# LedPlaneControl.net
KiCad netlist of a schematic drawn in Altium Designer
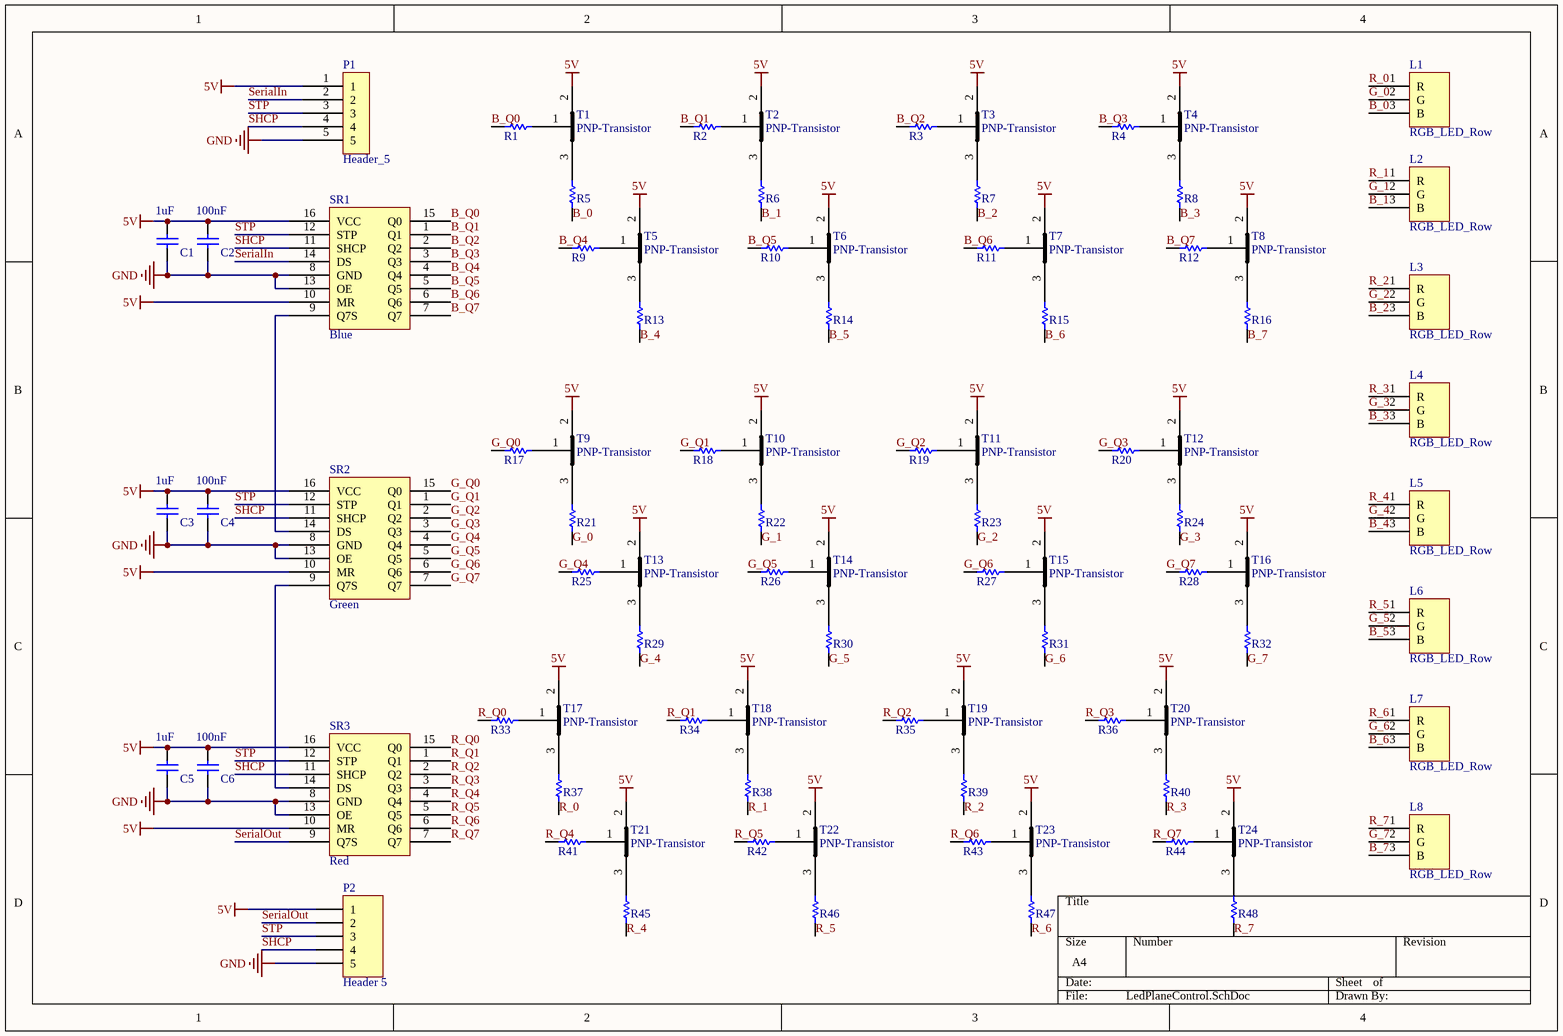
[diagram p0: LedPlaneControl.SchDoc]

(export (version "E")
  (design (tool "Eeschema 10.0.6"))
  (components
    (comp (ref "C1")
      (value "1uF")
      (footprint "CAPC1206(3216)190_L")
      (description "CAP 100nF 16V Â±1% 1206 (3216 Metric) Thickness 1.9mm SMD")
      (fields (field (name "TOLERANCE") "Â±1%") (field (name "Comment") "CAP 100nF 16V 1206(3216)"))
      (libsource (lib "Altium Content Vault") (part "CAP"))
    )
    (comp (ref "C2")
      (value "100nF")
      (footprint "CAPC1206(3216)190_L")
      (description "CAP 100nF 16V Â±1% 1206 (3216 Metric) Thickness 1.9mm SMD")
      (fields (field (name "TOLERANCE") "Â±1%") (field (name "Comment") "CAP 100nF 16V 1206(3216)"))
      (libsource (lib "Altium Content Vault") (part "CAP"))
    )
    (comp (ref "C3")
      (value "1uF")
      (footprint "CAPC1206(3216)190_L")
      (description "CAP 100nF 16V Â±1% 1206 (3216 Metric) Thickness 1.9mm SMD")
      (fields (field (name "TOLERANCE") "Â±1%") (field (name "Comment") "CAP 100nF 16V 1206(3216)"))
      (libsource (lib "Altium Content Vault") (part "CAP"))
    )
    (comp (ref "C4")
      (value "100nF")
      (footprint "CAPC1206(3216)190_L")
      (description "CAP 100nF 16V Â±1% 1206 (3216 Metric) Thickness 1.9mm SMD")
      (fields (field (name "TOLERANCE") "Â±1%") (field (name "Comment") "CAP 100nF 16V 1206(3216)"))
      (libsource (lib "Altium Content Vault") (part "CAP"))
    )
    (comp (ref "C5")
      (value "1uF")
      (footprint "CAPC1206(3216)190_L")
      (description "CAP 100nF 16V Â±1% 1206 (3216 Metric) Thickness 1.9mm SMD")
      (fields (field (name "TOLERANCE") "Â±1%") (field (name "Comment") "CAP 100nF 16V 1206(3216)"))
      (libsource (lib "Altium Content Vault") (part "CAP"))
    )
    (comp (ref "C6")
      (value "100nF")
      (footprint "CAPC1206(3216)190_L")
      (description "CAP 100nF 16V Â±1% 1206 (3216 Metric) Thickness 1.9mm SMD")
      (fields (field (name "TOLERANCE") "Â±1%") (field (name "Comment") "CAP 100nF 16V 1206(3216)"))
      (libsource (lib "Altium Content Vault") (part "CAP"))
    )
    (comp (ref "L1")
      (value "RGB_LED_Row")
      (footprint "LED_Row")
      (libsource (lib "RGB-Cube") (part "RGB_LED_Row"))
    )
    (comp (ref "L2")
      (value "RGB_LED_Row")
      (footprint "LED_Row")
      (libsource (lib "RGB-Cube") (part "RGB_LED_Row"))
    )
    (comp (ref "L3")
      (value "RGB_LED_Row")
      (footprint "LED_Row")
      (libsource (lib "RGB-Cube") (part "RGB_LED_Row"))
    )
    (comp (ref "L4")
      (value "RGB_LED_Row")
      (footprint "LED_Row")
      (libsource (lib "RGB-Cube") (part "RGB_LED_Row"))
    )
    (comp (ref "L5")
      (value "RGB_LED_Row")
      (footprint "LED_Row")
      (libsource (lib "RGB-Cube") (part "RGB_LED_Row"))
    )
    (comp (ref "L6")
      (value "RGB_LED_Row")
      (footprint "LED_Row")
      (libsource (lib "RGB-Cube") (part "RGB_LED_Row"))
    )
    (comp (ref "L7")
      (value "RGB_LED_Row")
      (footprint "LED_Row")
      (libsource (lib "RGB-Cube") (part "RGB_LED_Row"))
    )
    (comp (ref "L8")
      (value "RGB_LED_Row")
      (footprint "LED_Row")
      (libsource (lib "RGB-Cube") (part "RGB_LED_Row"))
    )
    (comp (ref "P1")
      (value "Header_5")
      (footprint "PinHeader")
      (libsource (lib "RGB-Cube") (part "Header_5"))
    )
    (comp (ref "P2")
      (value "Header 5")
      (footprint "HDR1X5")
      (description "Header, 5-Pin")
      (fields (field (name "PUBLISHER") "Altium Limited"))
      (libsource (lib "Miscellaneous Connectors") (part "Header 5"))
    )
    (comp (ref "R1")
      (value "43k 5% 1206(3216)")
      (footprint "RESC1206(3216)_M")
      (description "43k 0.25W 5% 1206 (3216 Metric)  SMD")
      (fields (field (name "TOLERANCE") "5 %") (field (name "POWER") "0.25 W"))
      (libsource (lib "Altium Content Vault") (part "CMP-1014-00009-1"))
    )
    (comp (ref "R2")
      (value "43k 5% 1206(3216)")
      (footprint "RESC1206(3216)_M")
      (description "43k 0.25W 5% 1206 (3216 Metric)  SMD")
      (fields (field (name "TOLERANCE") "5 %") (field (name "POWER") "0.25 W"))
      (libsource (lib "Altium Content Vault") (part "CMP-1014-00009-1"))
    )
    (comp (ref "R3")
      (value "43k 5% 1206(3216)")
      (footprint "RESC1206(3216)_M")
      (description "43k 0.25W 5% 1206 (3216 Metric)  SMD")
      (fields (field (name "TOLERANCE") "5 %") (field (name "POWER") "0.25 W"))
      (libsource (lib "Altium Content Vault") (part "CMP-1014-00009-1"))
    )
    (comp (ref "R4")
      (value "43k 5% 1206(3216)")
      (footprint "RESC1206(3216)_M")
      (description "43k 0.25W 5% 1206 (3216 Metric)  SMD")
      (fields (field (name "TOLERANCE") "5 %") (field (name "POWER") "0.25 W"))
      (libsource (lib "Altium Content Vault") (part "CMP-1014-00009-1"))
    )
    (comp (ref "R5")
      (value "2R 5% 1206(3216)")
      (footprint "RESC1206(3216)_M")
      (description "2R 0.25W 5% 1206 (3216 Metric)  SMD")
      (fields (field (name "TOLERANCE") "5 %") (field (name "POWER") "0.25 W"))
      (libsource (lib "Altium Content Vault") (part "CMP-1014-00009-1"))
    )
    (comp (ref "R6")
      (value "2R 5% 1206(3216)")
      (footprint "RESC1206(3216)_M")
      (description "2R 0.25W 5% 1206 (3216 Metric)  SMD")
      (fields (field (name "TOLERANCE") "5 %") (field (name "POWER") "0.25 W"))
      (libsource (lib "Altium Content Vault") (part "CMP-1014-00009-1"))
    )
    (comp (ref "R7")
      (value "2R 5% 1206(3216)")
      (footprint "RESC1206(3216)_M")
      (description "2R 0.25W 5% 1206 (3216 Metric)  SMD")
      (fields (field (name "TOLERANCE") "5 %") (field (name "POWER") "0.25 W"))
      (libsource (lib "Altium Content Vault") (part "CMP-1014-00009-1"))
    )
    (comp (ref "R8")
      (value "2R 5% 1206(3216)")
      (footprint "RESC1206(3216)_M")
      (description "2R 0.25W 5% 1206 (3216 Metric)  SMD")
      (fields (field (name "TOLERANCE") "5 %") (field (name "POWER") "0.25 W"))
      (libsource (lib "Altium Content Vault") (part "CMP-1014-00009-1"))
    )
    (comp (ref "R9")
      (value "43k 5% 1206(3216)")
      (footprint "RESC1206(3216)_M")
      (description "43k 0.25W 5% 1206 (3216 Metric)  SMD")
      (fields (field (name "TOLERANCE") "5 %") (field (name "POWER") "0.25 W"))
      (libsource (lib "Altium Content Vault") (part "CMP-1014-00009-1"))
    )
    (comp (ref "R10")
      (value "43k 5% 1206(3216)")
      (footprint "RESC1206(3216)_M")
      (description "43k 0.25W 5% 1206 (3216 Metric)  SMD")
      (fields (field (name "TOLERANCE") "5 %") (field (name "POWER") "0.25 W"))
      (libsource (lib "Altium Content Vault") (part "CMP-1014-00009-1"))
    )
    (comp (ref "R11")
      (value "43k 5% 1206(3216)")
      (footprint "RESC1206(3216)_M")
      (description "43k 0.25W 5% 1206 (3216 Metric)  SMD")
      (fields (field (name "TOLERANCE") "5 %") (field (name "POWER") "0.25 W"))
      (libsource (lib "Altium Content Vault") (part "CMP-1014-00009-1"))
    )
    (comp (ref "R12")
      (value "43k 5% 1206(3216)")
      (footprint "RESC1206(3216)_M")
      (description "43k 0.25W 5% 1206 (3216 Metric)  SMD")
      (fields (field (name "TOLERANCE") "5 %") (field (name "POWER") "0.25 W"))
      (libsource (lib "Altium Content Vault") (part "CMP-1014-00009-1"))
    )
    (comp (ref "R13")
      (value "2R 5% 1206(3216)")
      (footprint "RESC1206(3216)_M")
      (description "2R 0.25W 5% 1206 (3216 Metric)  SMD")
      (fields (field (name "TOLERANCE") "5 %") (field (name "POWER") "0.25 W"))
      (libsource (lib "Altium Content Vault") (part "CMP-1014-00009-1"))
    )
    (comp (ref "R14")
      (value "2R 5% 1206(3216)")
      (footprint "RESC1206(3216)_M")
      (description "2R 0.25W 5% 1206 (3216 Metric)  SMD")
      (fields (field (name "TOLERANCE") "5 %") (field (name "POWER") "0.25 W"))
      (libsource (lib "Altium Content Vault") (part "CMP-1014-00009-1"))
    )
    (comp (ref "R15")
      (value "2R 5% 1206(3216)")
      (footprint "RESC1206(3216)_M")
      (description "2R 0.25W 5% 1206 (3216 Metric)  SMD")
      (fields (field (name "TOLERANCE") "5 %") (field (name "POWER") "0.25 W"))
      (libsource (lib "Altium Content Vault") (part "CMP-1014-00009-1"))
    )
    (comp (ref "R16")
      (value "2R 5% 1206(3216)")
      (footprint "RESC1206(3216)_M")
      (description "2R 0.25W 5% 1206 (3216 Metric)  SMD")
      (fields (field (name "TOLERANCE") "5 %") (field (name "POWER") "0.25 W"))
      (libsource (lib "Altium Content Vault") (part "CMP-1014-00009-1"))
    )
    (comp (ref "R17")
      (value "43k 5% 1206(3216)")
      (footprint "RESC1206(3216)_M")
      (description "43k 0.25W 5% 1206 (3216 Metric)  SMD")
      (fields (field (name "TOLERANCE") "5 %") (field (name "POWER") "0.25 W"))
      (libsource (lib "Altium Content Vault") (part "CMP-1014-00009-1"))
    )
    (comp (ref "R18")
      (value "43k 5% 1206(3216)")
      (footprint "RESC1206(3216)_M")
      (description "43k 0.25W 5% 1206 (3216 Metric)  SMD")
      (fields (field (name "TOLERANCE") "5 %") (field (name "POWER") "0.25 W"))
      (libsource (lib "Altium Content Vault") (part "CMP-1014-00009-1"))
    )
    (comp (ref "R19")
      (value "43k 5% 1206(3216)")
      (footprint "RESC1206(3216)_M")
      (description "43k 0.25W 5% 1206 (3216 Metric)  SMD")
      (fields (field (name "TOLERANCE") "5 %") (field (name "POWER") "0.25 W"))
      (libsource (lib "Altium Content Vault") (part "CMP-1014-00009-1"))
    )
    (comp (ref "R20")
      (value "43k 5% 1206(3216)")
      (footprint "RESC1206(3216)_M")
      (description "43k 0.25W 5% 1206 (3216 Metric)  SMD")
      (fields (field (name "TOLERANCE") "5 %") (field (name "POWER") "0.25 W"))
      (libsource (lib "Altium Content Vault") (part "CMP-1014-00009-1"))
    )
    (comp (ref "R21")
      (value "2R 5% 1206(3216)")
      (footprint "RESC1206(3216)_M")
      (description "2R 0.25W 5% 1206 (3216 Metric)  SMD")
      (fields (field (name "TOLERANCE") "5 %") (field (name "POWER") "0.25 W"))
      (libsource (lib "Altium Content Vault") (part "CMP-1014-00009-1"))
    )
    (comp (ref "R22")
      (value "2R 5% 1206(3216)")
      (footprint "RESC1206(3216)_M")
      (description "2R 0.25W 5% 1206 (3216 Metric)  SMD")
      (fields (field (name "TOLERANCE") "5 %") (field (name "POWER") "0.25 W"))
      (libsource (lib "Altium Content Vault") (part "CMP-1014-00009-1"))
    )
    (comp (ref "R23")
      (value "2R 5% 1206(3216)")
      (footprint "RESC1206(3216)_M")
      (description "2R 0.25W 5% 1206 (3216 Metric)  SMD")
      (fields (field (name "TOLERANCE") "5 %") (field (name "POWER") "0.25 W"))
      (libsource (lib "Altium Content Vault") (part "CMP-1014-00009-1"))
    )
    (comp (ref "R24")
      (value "2R 5% 1206(3216)")
      (footprint "RESC1206(3216)_M")
      (description "2R 0.25W 5% 1206 (3216 Metric)  SMD")
      (fields (field (name "TOLERANCE") "5 %") (field (name "POWER") "0.25 W"))
      (libsource (lib "Altium Content Vault") (part "CMP-1014-00009-1"))
    )
    (comp (ref "R25")
      (value "43k 5% 1206(3216)")
      (footprint "RESC1206(3216)_M")
      (description "43k 0.25W 5% 1206 (3216 Metric)  SMD")
      (fields (field (name "TOLERANCE") "5 %") (field (name "POWER") "0.25 W"))
      (libsource (lib "Altium Content Vault") (part "CMP-1014-00009-1"))
    )
    (comp (ref "R26")
      (value "43k 5% 1206(3216)")
      (footprint "RESC1206(3216)_M")
      (description "43k 0.25W 5% 1206 (3216 Metric)  SMD")
      (fields (field (name "TOLERANCE") "5 %") (field (name "POWER") "0.25 W"))
      (libsource (lib "Altium Content Vault") (part "CMP-1014-00009-1"))
    )
    (comp (ref "R27")
      (value "43k 5% 1206(3216)")
      (footprint "RESC1206(3216)_M")
      (description "43k 0.25W 5% 1206 (3216 Metric)  SMD")
      (fields (field (name "TOLERANCE") "5 %") (field (name "POWER") "0.25 W"))
      (libsource (lib "Altium Content Vault") (part "CMP-1014-00009-1"))
    )
    (comp (ref "R28")
      (value "43k 5% 1206(3216)")
      (footprint "RESC1206(3216)_M")
      (description "43k 0.25W 5% 1206 (3216 Metric)  SMD")
      (fields (field (name "TOLERANCE") "5 %") (field (name "POWER") "0.25 W"))
      (libsource (lib "Altium Content Vault") (part "CMP-1014-00009-1"))
    )
    (comp (ref "R29")
      (value "2R 5% 1206(3216)")
      (footprint "RESC1206(3216)_M")
      (description "2R 0.25W 5% 1206 (3216 Metric)  SMD")
      (fields (field (name "TOLERANCE") "5 %") (field (name "POWER") "0.25 W"))
      (libsource (lib "Altium Content Vault") (part "CMP-1014-00009-1"))
    )
    (comp (ref "R30")
      (value "2R 5% 1206(3216)")
      (footprint "RESC1206(3216)_M")
      (description "2R 0.25W 5% 1206 (3216 Metric)  SMD")
      (fields (field (name "TOLERANCE") "5 %") (field (name "POWER") "0.25 W"))
      (libsource (lib "Altium Content Vault") (part "CMP-1014-00009-1"))
    )
    (comp (ref "R31")
      (value "2R 5% 1206(3216)")
      (footprint "RESC1206(3216)_M")
      (description "2R 0.25W 5% 1206 (3216 Metric)  SMD")
      (fields (field (name "TOLERANCE") "5 %") (field (name "POWER") "0.25 W"))
      (libsource (lib "Altium Content Vault") (part "CMP-1014-00009-1"))
    )
    (comp (ref "R32")
      (value "2R 5% 1206(3216)")
      (footprint "RESC1206(3216)_M")
      (description "2R 0.25W 5% 1206 (3216 Metric)  SMD")
      (fields (field (name "TOLERANCE") "5 %") (field (name "POWER") "0.25 W"))
      (libsource (lib "Altium Content Vault") (part "CMP-1014-00009-1"))
    )
    (comp (ref "R33")
      (value "43k 5% 1206(3216)")
      (footprint "RESC1206(3216)_M")
      (description "43k 0.25W 5% 1206 (3216 Metric)  SMD")
      (fields (field (name "TOLERANCE") "5 %") (field (name "POWER") "0.25 W"))
      (libsource (lib "Altium Content Vault") (part "CMP-1014-00009-1"))
    )
    (comp (ref "R34")
      (value "43k 5% 1206(3216)")
      (footprint "RESC1206(3216)_M")
      (description "43k 0.25W 5% 1206 (3216 Metric)  SMD")
      (fields (field (name "TOLERANCE") "5 %") (field (name "POWER") "0.25 W"))
      (libsource (lib "Altium Content Vault") (part "CMP-1014-00009-1"))
    )
    (comp (ref "R35")
      (value "43k 5% 1206(3216)")
      (footprint "RESC1206(3216)_M")
      (description "43k 0.25W 5% 1206 (3216 Metric)  SMD")
      (fields (field (name "TOLERANCE") "5 %") (field (name "POWER") "0.25 W"))
      (libsource (lib "Altium Content Vault") (part "CMP-1014-00009-1"))
    )
    (comp (ref "R36")
      (value "43k 5% 1206(3216)")
      (footprint "RESC1206(3216)_M")
      (description "43k 0.25W 5% 1206 (3216 Metric)  SMD")
      (fields (field (name "TOLERANCE") "5 %") (field (name "POWER") "0.25 W"))
      (libsource (lib "Altium Content Vault") (part "CMP-1014-00009-1"))
    )
    (comp (ref "R37")
      (value "2R 5% 1206(3216)")
      (footprint "RESC1206(3216)_M")
      (description "2R 0.25W 5% 1206 (3216 Metric)  SMD")
      (fields (field (name "TOLERANCE") "5 %") (field (name "POWER") "0.25 W"))
      (libsource (lib "Altium Content Vault") (part "CMP-1014-00009-1"))
    )
    (comp (ref "R38")
      (value "2R 5% 1206(3216)")
      (footprint "RESC1206(3216)_M")
      (description "2R 0.25W 5% 1206 (3216 Metric)  SMD")
      (fields (field (name "TOLERANCE") "5 %") (field (name "POWER") "0.25 W"))
      (libsource (lib "Altium Content Vault") (part "CMP-1014-00009-1"))
    )
    (comp (ref "R39")
      (value "2R 5% 1206(3216)")
      (footprint "RESC1206(3216)_M")
      (description "2R 0.25W 5% 1206 (3216 Metric)  SMD")
      (fields (field (name "TOLERANCE") "5 %") (field (name "POWER") "0.25 W"))
      (libsource (lib "Altium Content Vault") (part "CMP-1014-00009-1"))
    )
    (comp (ref "R40")
      (value "2R 5% 1206(3216)")
      (footprint "RESC1206(3216)_M")
      (description "2R 0.25W 5% 1206 (3216 Metric)  SMD")
      (fields (field (name "TOLERANCE") "5 %") (field (name "POWER") "0.25 W"))
      (libsource (lib "Altium Content Vault") (part "CMP-1014-00009-1"))
    )
    (comp (ref "R41")
      (value "43k 5% 1206(3216)")
      (footprint "RESC1206(3216)_M")
      (description "43k 0.25W 5% 1206 (3216 Metric)  SMD")
      (fields (field (name "TOLERANCE") "5 %") (field (name "POWER") "0.25 W"))
      (libsource (lib "Altium Content Vault") (part "CMP-1014-00009-1"))
    )
    (comp (ref "R42")
      (value "43k 5% 1206(3216)")
      (footprint "RESC1206(3216)_M")
      (description "43k 0.25W 5% 1206 (3216 Metric)  SMD")
      (fields (field (name "TOLERANCE") "5 %") (field (name "POWER") "0.25 W"))
      (libsource (lib "Altium Content Vault") (part "CMP-1014-00009-1"))
    )
    (comp (ref "R43")
      (value "43k 5% 1206(3216)")
      (footprint "RESC1206(3216)_M")
      (description "43k 0.25W 5% 1206 (3216 Metric)  SMD")
      (fields (field (name "TOLERANCE") "5 %") (field (name "POWER") "0.25 W"))
      (libsource (lib "Altium Content Vault") (part "CMP-1014-00009-1"))
    )
    (comp (ref "R44")
      (value "43k 5% 1206(3216)")
      (footprint "RESC1206(3216)_M")
      (description "43k 0.25W 5% 1206 (3216 Metric)  SMD")
      (fields (field (name "TOLERANCE") "5 %") (field (name "POWER") "0.25 W"))
      (libsource (lib "Altium Content Vault") (part "CMP-1014-00009-1"))
    )
    (comp (ref "R45")
      (value "2R 5% 1206(3216)")
      (footprint "RESC1206(3216)_M")
      (description "2R 0.25W 5% 1206 (3216 Metric)  SMD")
      (fields (field (name "TOLERANCE") "5 %") (field (name "POWER") "0.25 W"))
      (libsource (lib "Altium Content Vault") (part "CMP-1014-00009-1"))
    )
    (comp (ref "R46")
      (value "2R 5% 1206(3216)")
      (footprint "RESC1206(3216)_M")
      (description "2R 0.25W 5% 1206 (3216 Metric)  SMD")
      (fields (field (name "TOLERANCE") "5 %") (field (name "POWER") "0.25 W"))
      (libsource (lib "Altium Content Vault") (part "CMP-1014-00009-1"))
    )
    (comp (ref "R47")
      (value "2R 5% 1206(3216)")
      (footprint "RESC1206(3216)_M")
      (description "2R 0.25W 5% 1206 (3216 Metric)  SMD")
      (fields (field (name "TOLERANCE") "5 %") (field (name "POWER") "0.25 W"))
      (libsource (lib "Altium Content Vault") (part "CMP-1014-00009-1"))
    )
    (comp (ref "R48")
      (value "2R 5% 1206(3216)")
      (footprint "RESC1206(3216)_M")
      (description "2R 0.25W 5% 1206 (3216 Metric)  SMD")
      (fields (field (name "TOLERANCE") "5 %") (field (name "POWER") "0.25 W"))
      (libsource (lib "Altium Content Vault") (part "CMP-1014-00009-1"))
    )
    (comp (ref "SR1")
      (value "Blue")
      (footprint "SOP16")
      (description "74HC595 Farnell:  2098004")
      (libsource (lib "RGB-Cube") (part "74HC595"))
    )
    (comp (ref "SR2")
      (value "Green")
      (footprint "SOP16")
      (description "74HC595 Farnell:  2098004")
      (libsource (lib "RGB-Cube") (part "74HC595"))
    )
    (comp (ref "SR3")
      (value "Red")
      (footprint "SOP16")
      (description "74HC595 Farnell:  2098004")
      (libsource (lib "RGB-Cube") (part "74HC595"))
    )
    (comp (ref "T1")
      (value "PNP-Transistor")
      (footprint "SOT-223")
      (description "Reichelt: BCP 51-16 NXP")
      (libsource (lib "RGB-Cube") (part "PNP-Transistor"))
    )
    (comp (ref "T2")
      (value "PNP-Transistor")
      (footprint "SOT-223")
      (description "Reichelt: BCP 51-16 NXP")
      (libsource (lib "RGB-Cube") (part "PNP-Transistor"))
    )
    (comp (ref "T3")
      (value "PNP-Transistor")
      (footprint "SOT-223")
      (description "Reichelt: BCP 51-16 NXP")
      (libsource (lib "RGB-Cube") (part "PNP-Transistor"))
    )
    (comp (ref "T4")
      (value "PNP-Transistor")
      (footprint "SOT-223")
      (description "Reichelt: BCP 51-16 NXP")
      (libsource (lib "RGB-Cube") (part "PNP-Transistor"))
    )
    (comp (ref "T5")
      (value "PNP-Transistor")
      (footprint "SOT-223")
      (description "Reichelt: BCP 51-16 NXP")
      (libsource (lib "RGB-Cube") (part "PNP-Transistor"))
    )
    (comp (ref "T6")
      (value "PNP-Transistor")
      (footprint "SOT-223")
      (description "Reichelt: BCP 51-16 NXP")
      (libsource (lib "RGB-Cube") (part "PNP-Transistor"))
    )
    (comp (ref "T7")
      (value "PNP-Transistor")
      (footprint "SOT-223")
      (description "Reichelt: BCP 51-16 NXP")
      (libsource (lib "RGB-Cube") (part "PNP-Transistor"))
    )
    (comp (ref "T8")
      (value "PNP-Transistor")
      (footprint "SOT-223")
      (description "Reichelt: BCP 51-16 NXP")
      (libsource (lib "RGB-Cube") (part "PNP-Transistor"))
    )
    (comp (ref "T9")
      (value "PNP-Transistor")
      (footprint "SOT-223")
      (description "Reichelt: BCP 51-16 NXP")
      (libsource (lib "RGB-Cube") (part "PNP-Transistor"))
    )
    (comp (ref "T10")
      (value "PNP-Transistor")
      (footprint "SOT-223")
      (description "Reichelt: BCP 51-16 NXP")
      (libsource (lib "RGB-Cube") (part "PNP-Transistor"))
    )
    (comp (ref "T11")
      (value "PNP-Transistor")
      (footprint "SOT-223")
      (description "Reichelt: BCP 51-16 NXP")
      (libsource (lib "RGB-Cube") (part "PNP-Transistor"))
    )
    (comp (ref "T12")
      (value "PNP-Transistor")
      (footprint "SOT-223")
      (description "Reichelt: BCP 51-16 NXP")
      (libsource (lib "RGB-Cube") (part "PNP-Transistor"))
    )
    (comp (ref "T13")
      (value "PNP-Transistor")
      (footprint "SOT-223")
      (description "Reichelt: BCP 51-16 NXP")
      (libsource (lib "RGB-Cube") (part "PNP-Transistor"))
    )
    (comp (ref "T14")
      (value "PNP-Transistor")
      (footprint "SOT-223")
      (description "Reichelt: BCP 51-16 NXP")
      (libsource (lib "RGB-Cube") (part "PNP-Transistor"))
    )
    (comp (ref "T15")
      (value "PNP-Transistor")
      (footprint "SOT-223")
      (description "Reichelt: BCP 51-16 NXP")
      (libsource (lib "RGB-Cube") (part "PNP-Transistor"))
    )
    (comp (ref "T16")
      (value "PNP-Transistor")
      (footprint "SOT-223")
      (description "Reichelt: BCP 51-16 NXP")
      (libsource (lib "RGB-Cube") (part "PNP-Transistor"))
    )
    (comp (ref "T17")
      (value "PNP-Transistor")
      (footprint "SOT-223")
      (description "Reichelt: BCP 51-16 NXP")
      (libsource (lib "RGB-Cube") (part "PNP-Transistor"))
    )
    (comp (ref "T18")
      (value "PNP-Transistor")
      (footprint "SOT-223")
      (description "Reichelt: BCP 51-16 NXP")
      (libsource (lib "RGB-Cube") (part "PNP-Transistor"))
    )
    (comp (ref "T19")
      (value "PNP-Transistor")
      (footprint "SOT-223")
      (description "Reichelt: BCP 51-16 NXP")
      (libsource (lib "RGB-Cube") (part "PNP-Transistor"))
    )
    (comp (ref "T20")
      (value "PNP-Transistor")
      (footprint "SOT-223")
      (description "Reichelt: BCP 51-16 NXP")
      (libsource (lib "RGB-Cube") (part "PNP-Transistor"))
    )
    (comp (ref "T21")
      (value "PNP-Transistor")
      (footprint "SOT-223")
      (description "Reichelt: BCP 51-16 NXP")
      (libsource (lib "RGB-Cube") (part "PNP-Transistor"))
    )
    (comp (ref "T22")
      (value "PNP-Transistor")
      (footprint "SOT-223")
      (description "Reichelt: BCP 51-16 NXP")
      (libsource (lib "RGB-Cube") (part "PNP-Transistor"))
    )
    (comp (ref "T23")
      (value "PNP-Transistor")
      (footprint "SOT-223")
      (description "Reichelt: BCP 51-16 NXP")
      (libsource (lib "RGB-Cube") (part "PNP-Transistor"))
    )
    (comp (ref "T24")
      (value "PNP-Transistor")
      (footprint "SOT-223")
      (description "Reichelt: BCP 51-16 NXP")
      (libsource (lib "RGB-Cube") (part "PNP-Transistor"))
    )
  )
  (nets
    (net (code "2") (name "/B_0") (class "Default")
      (node (ref "L1") (pin "3") (pinfunction "B_3") (pintype "passive"))
      (node (ref "R5") (pin "1") (pinfunction "1_1") (pintype "passive"))
    )
    (net (code "3") (name "/B_1") (class "Default")
      (node (ref "L2") (pin "3") (pinfunction "B_3") (pintype "passive"))
      (node (ref "R6") (pin "1") (pinfunction "1_1") (pintype "passive"))
    )
    (net (code "4") (name "/B_2") (class "Default")
      (node (ref "L3") (pin "3") (pinfunction "B_3") (pintype "passive"))
      (node (ref "R7") (pin "1") (pinfunction "1_1") (pintype "passive"))
    )
    (net (code "5") (name "/B_3") (class "Default")
      (node (ref "L4") (pin "3") (pinfunction "B_3") (pintype "passive"))
      (node (ref "R8") (pin "1") (pinfunction "1_1") (pintype "passive"))
    )
    (net (code "6") (name "/B_4") (class "Default")
      (node (ref "L5") (pin "3") (pinfunction "B_3") (pintype "passive"))
      (node (ref "R13") (pin "1") (pinfunction "1_1") (pintype "passive"))
    )
    (net (code "7") (name "/B_5") (class "Default")
      (node (ref "L6") (pin "3") (pinfunction "B_3") (pintype "passive"))
      (node (ref "R14") (pin "1") (pinfunction "1_1") (pintype "passive"))
    )
    (net (code "8") (name "/B_6") (class "Default")
      (node (ref "L7") (pin "3") (pinfunction "B_3") (pintype "passive"))
      (node (ref "R15") (pin "1") (pinfunction "1_1") (pintype "passive"))
    )
    (net (code "9") (name "/B_7") (class "Default")
      (node (ref "L8") (pin "3") (pinfunction "B_3") (pintype "passive"))
      (node (ref "R16") (pin "1") (pinfunction "1_1") (pintype "passive"))
    )
    (net (code "10") (name "/B_Q0") (class "Default")
      (node (ref "R1") (pin "1") (pinfunction "1_1") (pintype "passive"))
      (node (ref "SR1") (pin "15") (pinfunction "Q0_15") (pintype "passive"))
    )
    (net (code "11") (name "/B_Q1") (class "Default")
      (node (ref "R2") (pin "1") (pinfunction "1_1") (pintype "passive"))
      (node (ref "SR1") (pin "1") (pinfunction "Q1_1") (pintype "passive"))
    )
    (net (code "12") (name "/B_Q2") (class "Default")
      (node (ref "R3") (pin "1") (pinfunction "1_1") (pintype "passive"))
      (node (ref "SR1") (pin "2") (pinfunction "Q2_2") (pintype "passive"))
    )
    (net (code "13") (name "/B_Q3") (class "Default")
      (node (ref "R4") (pin "1") (pinfunction "1_1") (pintype "passive"))
      (node (ref "SR1") (pin "3") (pinfunction "Q3_3") (pintype "passive"))
    )
    (net (code "14") (name "/B_Q4") (class "Default")
      (node (ref "R9") (pin "1") (pinfunction "1_1") (pintype "passive"))
      (node (ref "SR1") (pin "4") (pinfunction "Q4_4") (pintype "passive"))
    )
    (net (code "15") (name "/B_Q5") (class "Default")
      (node (ref "R10") (pin "1") (pinfunction "1_1") (pintype "passive"))
      (node (ref "SR1") (pin "5") (pinfunction "Q5_5") (pintype "passive"))
    )
    (net (code "16") (name "/B_Q6") (class "Default")
      (node (ref "R11") (pin "1") (pinfunction "1_1") (pintype "passive"))
      (node (ref "SR1") (pin "6") (pinfunction "Q6_6") (pintype "passive"))
    )
    (net (code "17") (name "/B_Q7") (class "Default")
      (node (ref "R12") (pin "1") (pinfunction "1_1") (pintype "passive"))
      (node (ref "SR1") (pin "7") (pinfunction "Q7_7") (pintype "passive"))
    )
    (net (code "18") (name "/G_0") (class "Default")
      (node (ref "L1") (pin "2") (pinfunction "G_2") (pintype "passive"))
      (node (ref "R21") (pin "1") (pinfunction "1_1") (pintype "passive"))
    )
    (net (code "19") (name "/G_1") (class "Default")
      (node (ref "L2") (pin "2") (pinfunction "G_2") (pintype "passive"))
      (node (ref "R22") (pin "1") (pinfunction "1_1") (pintype "passive"))
    )
    (net (code "20") (name "/G_2") (class "Default")
      (node (ref "L3") (pin "2") (pinfunction "G_2") (pintype "passive"))
      (node (ref "R23") (pin "1") (pinfunction "1_1") (pintype "passive"))
    )
    (net (code "21") (name "/G_3") (class "Default")
      (node (ref "L4") (pin "2") (pinfunction "G_2") (pintype "passive"))
      (node (ref "R24") (pin "1") (pinfunction "1_1") (pintype "passive"))
    )
    (net (code "22") (name "/G_4") (class "Default")
      (node (ref "L5") (pin "2") (pinfunction "G_2") (pintype "passive"))
      (node (ref "R29") (pin "1") (pinfunction "1_1") (pintype "passive"))
    )
    (net (code "23") (name "/G_5") (class "Default")
      (node (ref "L6") (pin "2") (pinfunction "G_2") (pintype "passive"))
      (node (ref "R30") (pin "1") (pinfunction "1_1") (pintype "passive"))
    )
    (net (code "24") (name "/G_6") (class "Default")
      (node (ref "L7") (pin "2") (pinfunction "G_2") (pintype "passive"))
      (node (ref "R31") (pin "1") (pinfunction "1_1") (pintype "passive"))
    )
    (net (code "25") (name "/G_7") (class "Default")
      (node (ref "L8") (pin "2") (pinfunction "G_2") (pintype "passive"))
      (node (ref "R32") (pin "1") (pinfunction "1_1") (pintype "passive"))
    )
    (net (code "26") (name "/G_Q0") (class "Default")
      (node (ref "R17") (pin "1") (pinfunction "1_1") (pintype "passive"))
      (node (ref "SR2") (pin "15") (pinfunction "Q0_15") (pintype "passive"))
    )
    (net (code "27") (name "/G_Q1") (class "Default")
      (node (ref "R18") (pin "1") (pinfunction "1_1") (pintype "passive"))
      (node (ref "SR2") (pin "1") (pinfunction "Q1_1") (pintype "passive"))
    )
    (net (code "28") (name "/G_Q2") (class "Default")
      (node (ref "R19") (pin "1") (pinfunction "1_1") (pintype "passive"))
      (node (ref "SR2") (pin "2") (pinfunction "Q2_2") (pintype "passive"))
    )
    (net (code "29") (name "/G_Q3") (class "Default")
      (node (ref "R20") (pin "1") (pinfunction "1_1") (pintype "passive"))
      (node (ref "SR2") (pin "3") (pinfunction "Q3_3") (pintype "passive"))
    )
    (net (code "30") (name "/G_Q4") (class "Default")
      (node (ref "R25") (pin "1") (pinfunction "1_1") (pintype "passive"))
      (node (ref "SR2") (pin "4") (pinfunction "Q4_4") (pintype "passive"))
    )
    (net (code "31") (name "/G_Q5") (class "Default")
      (node (ref "R26") (pin "1") (pinfunction "1_1") (pintype "passive"))
      (node (ref "SR2") (pin "5") (pinfunction "Q5_5") (pintype "passive"))
    )
    (net (code "32") (name "/G_Q6") (class "Default")
      (node (ref "R27") (pin "1") (pinfunction "1_1") (pintype "passive"))
      (node (ref "SR2") (pin "6") (pinfunction "Q6_6") (pintype "passive"))
    )
    (net (code "33") (name "/G_Q7") (class "Default")
      (node (ref "R28") (pin "1") (pinfunction "1_1") (pintype "passive"))
      (node (ref "SR2") (pin "7") (pinfunction "Q7_7") (pintype "passive"))
    )
    (net (code "34") (name "/R_0") (class "Default")
      (node (ref "L1") (pin "1") (pinfunction "R_1") (pintype "passive"))
      (node (ref "R37") (pin "1") (pinfunction "1_1") (pintype "passive"))
    )
    (net (code "35") (name "/R_1") (class "Default")
      (node (ref "L2") (pin "1") (pinfunction "R_1") (pintype "passive"))
      (node (ref "R38") (pin "1") (pinfunction "1_1") (pintype "passive"))
    )
    (net (code "36") (name "/R_2") (class "Default")
      (node (ref "L3") (pin "1") (pinfunction "R_1") (pintype "passive"))
      (node (ref "R39") (pin "1") (pinfunction "1_1") (pintype "passive"))
    )
    (net (code "37") (name "/R_3") (class "Default")
      (node (ref "L4") (pin "1") (pinfunction "R_1") (pintype "passive"))
      (node (ref "R40") (pin "1") (pinfunction "1_1") (pintype "passive"))
    )
    (net (code "38") (name "/R_4") (class "Default")
      (node (ref "L5") (pin "1") (pinfunction "R_1") (pintype "passive"))
      (node (ref "R45") (pin "1") (pinfunction "1_1") (pintype "passive"))
    )
    (net (code "39") (name "/R_5") (class "Default")
      (node (ref "L6") (pin "1") (pinfunction "R_1") (pintype "passive"))
      (node (ref "R46") (pin "1") (pinfunction "1_1") (pintype "passive"))
    )
    (net (code "40") (name "/R_6") (class "Default")
      (node (ref "L7") (pin "1") (pinfunction "R_1") (pintype "passive"))
      (node (ref "R47") (pin "1") (pinfunction "1_1") (pintype "passive"))
    )
    (net (code "41") (name "/R_7") (class "Default")
      (node (ref "L8") (pin "1") (pinfunction "R_1") (pintype "passive"))
      (node (ref "R48") (pin "1") (pinfunction "1_1") (pintype "passive"))
    )
    (net (code "42") (name "/R_Q0") (class "Default")
      (node (ref "R33") (pin "1") (pinfunction "1_1") (pintype "passive"))
      (node (ref "SR3") (pin "15") (pinfunction "Q0_15") (pintype "passive"))
    )
    (net (code "43") (name "/R_Q1") (class "Default")
      (node (ref "R34") (pin "1") (pinfunction "1_1") (pintype "passive"))
      (node (ref "SR3") (pin "1") (pinfunction "Q1_1") (pintype "passive"))
    )
    (net (code "44") (name "/R_Q2") (class "Default")
      (node (ref "R35") (pin "1") (pinfunction "1_1") (pintype "passive"))
      (node (ref "SR3") (pin "2") (pinfunction "Q2_2") (pintype "passive"))
    )
    (net (code "45") (name "/R_Q3") (class "Default")
      (node (ref "R36") (pin "1") (pinfunction "1_1") (pintype "passive"))
      (node (ref "SR3") (pin "3") (pinfunction "Q3_3") (pintype "passive"))
    )
    (net (code "46") (name "/R_Q4") (class "Default")
      (node (ref "R41") (pin "1") (pinfunction "1_1") (pintype "passive"))
      (node (ref "SR3") (pin "4") (pinfunction "Q4_4") (pintype "passive"))
    )
    (net (code "47") (name "/R_Q5") (class "Default")
      (node (ref "R42") (pin "1") (pinfunction "1_1") (pintype "passive"))
      (node (ref "SR3") (pin "5") (pinfunction "Q5_5") (pintype "passive"))
    )
    (net (code "48") (name "/R_Q6") (class "Default")
      (node (ref "R43") (pin "1") (pinfunction "1_1") (pintype "passive"))
      (node (ref "SR3") (pin "6") (pinfunction "Q6_6") (pintype "passive"))
    )
    (net (code "49") (name "/R_Q7") (class "Default")
      (node (ref "R44") (pin "1") (pinfunction "1_1") (pintype "passive"))
      (node (ref "SR3") (pin "7") (pinfunction "Q7_7") (pintype "passive"))
    )
    (net (code "50") (name "/SHCP") (class "Default")
      (node (ref "P1") (pin "4") (pinfunction "4_4") (pintype "passive"))
      (node (ref "P2") (pin "4") (pinfunction "4_4") (pintype "passive"))
      (node (ref "SR1") (pin "11") (pinfunction "SHCP_11") (pintype "passive"))
      (node (ref "SR2") (pin "11") (pinfunction "SHCP_11") (pintype "passive"))
      (node (ref "SR3") (pin "11") (pinfunction "SHCP_11") (pintype "passive"))
    )
    (net (code "51") (name "/STP") (class "Default")
      (node (ref "P1") (pin "3") (pinfunction "3_3") (pintype "passive"))
      (node (ref "P2") (pin "3") (pinfunction "3_3") (pintype "passive"))
      (node (ref "SR1") (pin "12") (pinfunction "STP_12") (pintype "passive"))
      (node (ref "SR2") (pin "12") (pinfunction "STP_12") (pintype "passive"))
      (node (ref "SR3") (pin "12") (pinfunction "STP_12") (pintype "passive"))
    )
    (net (code "52") (name "/SerialIn") (class "Default")
      (node (ref "P1") (pin "2") (pinfunction "2_2") (pintype "passive"))
      (node (ref "SR1") (pin "14") (pinfunction "DS_14") (pintype "passive"))
    )
    (net (code "53") (name "/SerialOut") (class "Default")
      (node (ref "P2") (pin "2") (pinfunction "2_2") (pintype "passive"))
      (node (ref "SR3") (pin "9") (pinfunction "Q7S_9") (pintype "passive"))
    )
    (net (code "54") (name "5V") (class "Default")
      (node (ref "C1") (pin "1") (pinfunction "1_1") (pintype "passive"))
      (node (ref "C2") (pin "1") (pinfunction "1_1") (pintype "passive"))
      (node (ref "C3") (pin "1") (pinfunction "1_1") (pintype "passive"))
      (node (ref "C4") (pin "1") (pinfunction "1_1") (pintype "passive"))
      (node (ref "C5") (pin "1") (pinfunction "1_1") (pintype "passive"))
      (node (ref "C6") (pin "1") (pinfunction "1_1") (pintype "passive"))
      (node (ref "P1") (pin "1") (pinfunction "1_1") (pintype "passive"))
      (node (ref "P2") (pin "1") (pinfunction "1_1") (pintype "passive"))
      (node (ref "SR1") (pin "10") (pinfunction "MR_10") (pintype "passive"))
      (node (ref "SR1") (pin "16") (pinfunction "VCC_16") (pintype "passive"))
      (node (ref "SR2") (pin "10") (pinfunction "MR_10") (pintype "passive"))
      (node (ref "SR2") (pin "16") (pinfunction "VCC_16") (pintype "passive"))
      (node (ref "SR3") (pin "10") (pinfunction "MR_10") (pintype "passive"))
      (node (ref "SR3") (pin "16") (pinfunction "VCC_16") (pintype "passive"))
      (node (ref "T1") (pin "2") (pinfunction "Collector_2") (pintype "passive"))
      (node (ref "T10") (pin "2") (pinfunction "Collector_2") (pintype "passive"))
      (node (ref "T11") (pin "2") (pinfunction "Collector_2") (pintype "passive"))
      (node (ref "T12") (pin "2") (pinfunction "Collector_2") (pintype "passive"))
      (node (ref "T13") (pin "2") (pinfunction "Collector_2") (pintype "passive"))
      (node (ref "T14") (pin "2") (pinfunction "Collector_2") (pintype "passive"))
      (node (ref "T15") (pin "2") (pinfunction "Collector_2") (pintype "passive"))
      (node (ref "T16") (pin "2") (pinfunction "Collector_2") (pintype "passive"))
      (node (ref "T17") (pin "2") (pinfunction "Collector_2") (pintype "passive"))
      (node (ref "T18") (pin "2") (pinfunction "Collector_2") (pintype "passive"))
      (node (ref "T19") (pin "2") (pinfunction "Collector_2") (pintype "passive"))
      (node (ref "T2") (pin "2") (pinfunction "Collector_2") (pintype "passive"))
      (node (ref "T20") (pin "2") (pinfunction "Collector_2") (pintype "passive"))
      (node (ref "T21") (pin "2") (pinfunction "Collector_2") (pintype "passive"))
      (node (ref "T22") (pin "2") (pinfunction "Collector_2") (pintype "passive"))
      (node (ref "T23") (pin "2") (pinfunction "Collector_2") (pintype "passive"))
      (node (ref "T24") (pin "2") (pinfunction "Collector_2") (pintype "passive"))
      (node (ref "T3") (pin "2") (pinfunction "Collector_2") (pintype "passive"))
      (node (ref "T4") (pin "2") (pinfunction "Collector_2") (pintype "passive"))
      (node (ref "T5") (pin "2") (pinfunction "Collector_2") (pintype "passive"))
      (node (ref "T6") (pin "2") (pinfunction "Collector_2") (pintype "passive"))
      (node (ref "T7") (pin "2") (pinfunction "Collector_2") (pintype "passive"))
      (node (ref "T8") (pin "2") (pinfunction "Collector_2") (pintype "passive"))
      (node (ref "T9") (pin "2") (pinfunction "Collector_2") (pintype "passive"))
    )
    (net (code "55") (name "GND") (class "Default")
      (node (ref "C1") (pin "2") (pinfunction "2_2") (pintype "passive"))
      (node (ref "C2") (pin "2") (pinfunction "2_2") (pintype "passive"))
      (node (ref "C3") (pin "2") (pinfunction "2_2") (pintype "passive"))
      (node (ref "C4") (pin "2") (pinfunction "2_2") (pintype "passive"))
      (node (ref "C5") (pin "2") (pinfunction "2_2") (pintype "passive"))
      (node (ref "C6") (pin "2") (pinfunction "2_2") (pintype "passive"))
      (node (ref "P1") (pin "5") (pinfunction "5_5") (pintype "passive"))
      (node (ref "P2") (pin "5") (pinfunction "5_5") (pintype "passive"))
      (node (ref "SR1") (pin "13") (pinfunction "OE_13") (pintype "passive"))
      (node (ref "SR1") (pin "8") (pinfunction "GND_8") (pintype "passive"))
      (node (ref "SR2") (pin "13") (pinfunction "OE_13") (pintype "passive"))
      (node (ref "SR2") (pin "8") (pinfunction "GND_8") (pintype "passive"))
      (node (ref "SR3") (pin "13") (pinfunction "OE_13") (pintype "passive"))
      (node (ref "SR3") (pin "8") (pinfunction "GND_8") (pintype "passive"))
    )
    (net (code "56") (name "Net-(SR1-Q7S)") (class "Default")
      (node (ref "SR1") (pin "9") (pinfunction "Q7S_9") (pintype "passive"))
      (node (ref "SR2") (pin "14") (pinfunction "DS_14") (pintype "passive"))
    )
    (net (code "57") (name "Net-(SR2-Q7S)") (class "Default")
      (node (ref "SR2") (pin "9") (pinfunction "Q7S_9") (pintype "passive"))
      (node (ref "SR3") (pin "14") (pinfunction "DS_14") (pintype "passive"))
    )
    (net (code "58") (name "Net-(T1-Base)") (class "Default")
      (node (ref "R1") (pin "2") (pinfunction "2_2") (pintype "passive"))
      (node (ref "T1") (pin "1") (pinfunction "Base_1") (pintype "passive"))
    )
    (net (code "59") (name "Net-(T1-Emitter)") (class "Default")
      (node (ref "R5") (pin "2") (pinfunction "2_2") (pintype "passive"))
      (node (ref "T1") (pin "3") (pinfunction "Emitter_3") (pintype "passive"))
    )
    (net (code "60") (name "Net-(T2-Base)") (class "Default")
      (node (ref "R2") (pin "2") (pinfunction "2_2") (pintype "passive"))
      (node (ref "T2") (pin "1") (pinfunction "Base_1") (pintype "passive"))
    )
    (net (code "61") (name "Net-(T2-Emitter)") (class "Default")
      (node (ref "R6") (pin "2") (pinfunction "2_2") (pintype "passive"))
      (node (ref "T2") (pin "3") (pinfunction "Emitter_3") (pintype "passive"))
    )
    (net (code "62") (name "Net-(T3-Base)") (class "Default")
      (node (ref "R3") (pin "2") (pinfunction "2_2") (pintype "passive"))
      (node (ref "T3") (pin "1") (pinfunction "Base_1") (pintype "passive"))
    )
    (net (code "63") (name "Net-(T3-Emitter)") (class "Default")
      (node (ref "R7") (pin "2") (pinfunction "2_2") (pintype "passive"))
      (node (ref "T3") (pin "3") (pinfunction "Emitter_3") (pintype "passive"))
    )
    (net (code "64") (name "Net-(T4-Base)") (class "Default")
      (node (ref "R4") (pin "2") (pinfunction "2_2") (pintype "passive"))
      (node (ref "T4") (pin "1") (pinfunction "Base_1") (pintype "passive"))
    )
    (net (code "65") (name "Net-(T4-Emitter)") (class "Default")
      (node (ref "R8") (pin "2") (pinfunction "2_2") (pintype "passive"))
      (node (ref "T4") (pin "3") (pinfunction "Emitter_3") (pintype "passive"))
    )
    (net (code "66") (name "Net-(T5-Base)") (class "Default")
      (node (ref "R9") (pin "2") (pinfunction "2_2") (pintype "passive"))
      (node (ref "T5") (pin "1") (pinfunction "Base_1") (pintype "passive"))
    )
    (net (code "67") (name "Net-(T5-Emitter)") (class "Default")
      (node (ref "R13") (pin "2") (pinfunction "2_2") (pintype "passive"))
      (node (ref "T5") (pin "3") (pinfunction "Emitter_3") (pintype "passive"))
    )
    (net (code "68") (name "Net-(T6-Base)") (class "Default")
      (node (ref "R10") (pin "2") (pinfunction "2_2") (pintype "passive"))
      (node (ref "T6") (pin "1") (pinfunction "Base_1") (pintype "passive"))
    )
    (net (code "69") (name "Net-(T6-Emitter)") (class "Default")
      (node (ref "R14") (pin "2") (pinfunction "2_2") (pintype "passive"))
      (node (ref "T6") (pin "3") (pinfunction "Emitter_3") (pintype "passive"))
    )
    (net (code "70") (name "Net-(T7-Base)") (class "Default")
      (node (ref "R11") (pin "2") (pinfunction "2_2") (pintype "passive"))
      (node (ref "T7") (pin "1") (pinfunction "Base_1") (pintype "passive"))
    )
    (net (code "71") (name "Net-(T7-Emitter)") (class "Default")
      (node (ref "R15") (pin "2") (pinfunction "2_2") (pintype "passive"))
      (node (ref "T7") (pin "3") (pinfunction "Emitter_3") (pintype "passive"))
    )
    (net (code "72") (name "Net-(T8-Base)") (class "Default")
      (node (ref "R12") (pin "2") (pinfunction "2_2") (pintype "passive"))
      (node (ref "T8") (pin "1") (pinfunction "Base_1") (pintype "passive"))
    )
    (net (code "73") (name "Net-(T8-Emitter)") (class "Default")
      (node (ref "R16") (pin "2") (pinfunction "2_2") (pintype "passive"))
      (node (ref "T8") (pin "3") (pinfunction "Emitter_3") (pintype "passive"))
    )
    (net (code "74") (name "Net-(T9-Base)") (class "Default")
      (node (ref "R17") (pin "2") (pinfunction "2_2") (pintype "passive"))
      (node (ref "T9") (pin "1") (pinfunction "Base_1") (pintype "passive"))
    )
    (net (code "75") (name "Net-(T9-Emitter)") (class "Default")
      (node (ref "R21") (pin "2") (pinfunction "2_2") (pintype "passive"))
      (node (ref "T9") (pin "3") (pinfunction "Emitter_3") (pintype "passive"))
    )
    (net (code "76") (name "Net-(T10-Base)") (class "Default")
      (node (ref "R18") (pin "2") (pinfunction "2_2") (pintype "passive"))
      (node (ref "T10") (pin "1") (pinfunction "Base_1") (pintype "passive"))
    )
    (net (code "77") (name "Net-(T10-Emitter)") (class "Default")
      (node (ref "R22") (pin "2") (pinfunction "2_2") (pintype "passive"))
      (node (ref "T10") (pin "3") (pinfunction "Emitter_3") (pintype "passive"))
    )
    (net (code "78") (name "Net-(T11-Base)") (class "Default")
      (node (ref "R19") (pin "2") (pinfunction "2_2") (pintype "passive"))
      (node (ref "T11") (pin "1") (pinfunction "Base_1") (pintype "passive"))
    )
    (net (code "79") (name "Net-(T11-Emitter)") (class "Default")
      (node (ref "R23") (pin "2") (pinfunction "2_2") (pintype "passive"))
      (node (ref "T11") (pin "3") (pinfunction "Emitter_3") (pintype "passive"))
    )
    (net (code "80") (name "Net-(T12-Base)") (class "Default")
      (node (ref "R20") (pin "2") (pinfunction "2_2") (pintype "passive"))
      (node (ref "T12") (pin "1") (pinfunction "Base_1") (pintype "passive"))
    )
    (net (code "81") (name "Net-(T12-Emitter)") (class "Default")
      (node (ref "R24") (pin "2") (pinfunction "2_2") (pintype "passive"))
      (node (ref "T12") (pin "3") (pinfunction "Emitter_3") (pintype "passive"))
    )
    (net (code "82") (name "Net-(T13-Base)") (class "Default")
      (node (ref "R25") (pin "2") (pinfunction "2_2") (pintype "passive"))
      (node (ref "T13") (pin "1") (pinfunction "Base_1") (pintype "passive"))
    )
    (net (code "83") (name "Net-(T13-Emitter)") (class "Default")
      (node (ref "R29") (pin "2") (pinfunction "2_2") (pintype "passive"))
      (node (ref "T13") (pin "3") (pinfunction "Emitter_3") (pintype "passive"))
    )
    (net (code "84") (name "Net-(T14-Base)") (class "Default")
      (node (ref "R26") (pin "2") (pinfunction "2_2") (pintype "passive"))
      (node (ref "T14") (pin "1") (pinfunction "Base_1") (pintype "passive"))
    )
    (net (code "85") (name "Net-(T14-Emitter)") (class "Default")
      (node (ref "R30") (pin "2") (pinfunction "2_2") (pintype "passive"))
      (node (ref "T14") (pin "3") (pinfunction "Emitter_3") (pintype "passive"))
    )
    (net (code "86") (name "Net-(T15-Base)") (class "Default")
      (node (ref "R27") (pin "2") (pinfunction "2_2") (pintype "passive"))
      (node (ref "T15") (pin "1") (pinfunction "Base_1") (pintype "passive"))
    )
    (net (code "87") (name "Net-(T15-Emitter)") (class "Default")
      (node (ref "R31") (pin "2") (pinfunction "2_2") (pintype "passive"))
      (node (ref "T15") (pin "3") (pinfunction "Emitter_3") (pintype "passive"))
    )
    (net (code "88") (name "Net-(T16-Base)") (class "Default")
      (node (ref "R28") (pin "2") (pinfunction "2_2") (pintype "passive"))
      (node (ref "T16") (pin "1") (pinfunction "Base_1") (pintype "passive"))
    )
    (net (code "89") (name "Net-(T16-Emitter)") (class "Default")
      (node (ref "R32") (pin "2") (pinfunction "2_2") (pintype "passive"))
      (node (ref "T16") (pin "3") (pinfunction "Emitter_3") (pintype "passive"))
    )
    (net (code "90") (name "Net-(T17-Base)") (class "Default")
      (node (ref "R33") (pin "2") (pinfunction "2_2") (pintype "passive"))
      (node (ref "T17") (pin "1") (pinfunction "Base_1") (pintype "passive"))
    )
    (net (code "91") (name "Net-(T17-Emitter)") (class "Default")
      (node (ref "R37") (pin "2") (pinfunction "2_2") (pintype "passive"))
      (node (ref "T17") (pin "3") (pinfunction "Emitter_3") (pintype "passive"))
    )
    (net (code "92") (name "Net-(T18-Base)") (class "Default")
      (node (ref "R34") (pin "2") (pinfunction "2_2") (pintype "passive"))
      (node (ref "T18") (pin "1") (pinfunction "Base_1") (pintype "passive"))
    )
    (net (code "93") (name "Net-(T18-Emitter)") (class "Default")
      (node (ref "R38") (pin "2") (pinfunction "2_2") (pintype "passive"))
      (node (ref "T18") (pin "3") (pinfunction "Emitter_3") (pintype "passive"))
    )
    (net (code "94") (name "Net-(T19-Base)") (class "Default")
      (node (ref "R35") (pin "2") (pinfunction "2_2") (pintype "passive"))
      (node (ref "T19") (pin "1") (pinfunction "Base_1") (pintype "passive"))
    )
    (net (code "95") (name "Net-(T19-Emitter)") (class "Default")
      (node (ref "R39") (pin "2") (pinfunction "2_2") (pintype "passive"))
      (node (ref "T19") (pin "3") (pinfunction "Emitter_3") (pintype "passive"))
    )
    (net (code "96") (name "Net-(T20-Base)") (class "Default")
      (node (ref "R36") (pin "2") (pinfunction "2_2") (pintype "passive"))
      (node (ref "T20") (pin "1") (pinfunction "Base_1") (pintype "passive"))
    )
    (net (code "97") (name "Net-(T20-Emitter)") (class "Default")
      (node (ref "R40") (pin "2") (pinfunction "2_2") (pintype "passive"))
      (node (ref "T20") (pin "3") (pinfunction "Emitter_3") (pintype "passive"))
    )
    (net (code "98") (name "Net-(T21-Base)") (class "Default")
      (node (ref "R41") (pin "2") (pinfunction "2_2") (pintype "passive"))
      (node (ref "T21") (pin "1") (pinfunction "Base_1") (pintype "passive"))
    )
    (net (code "99") (name "Net-(T21-Emitter)") (class "Default")
      (node (ref "R45") (pin "2") (pinfunction "2_2") (pintype "passive"))
      (node (ref "T21") (pin "3") (pinfunction "Emitter_3") (pintype "passive"))
    )
    (net (code "100") (name "Net-(T22-Base)") (class "Default")
      (node (ref "R42") (pin "2") (pinfunction "2_2") (pintype "passive"))
      (node (ref "T22") (pin "1") (pinfunction "Base_1") (pintype "passive"))
    )
    (net (code "101") (name "Net-(T22-Emitter)") (class "Default")
      (node (ref "R46") (pin "2") (pinfunction "2_2") (pintype "passive"))
      (node (ref "T22") (pin "3") (pinfunction "Emitter_3") (pintype "passive"))
    )
    (net (code "102") (name "Net-(T23-Base)") (class "Default")
      (node (ref "R43") (pin "2") (pinfunction "2_2") (pintype "passive"))
      (node (ref "T23") (pin "1") (pinfunction "Base_1") (pintype "passive"))
    )
    (net (code "103") (name "Net-(T23-Emitter)") (class "Default")
      (node (ref "R47") (pin "2") (pinfunction "2_2") (pintype "passive"))
      (node (ref "T23") (pin "3") (pinfunction "Emitter_3") (pintype "passive"))
    )
    (net (code "104") (name "Net-(T24-Base)") (class "Default")
      (node (ref "R44") (pin "2") (pinfunction "2_2") (pintype "passive"))
      (node (ref "T24") (pin "1") (pinfunction "Base_1") (pintype "passive"))
    )
    (net (code "105") (name "Net-(T24-Emitter)") (class "Default")
      (node (ref "R48") (pin "2") (pinfunction "2_2") (pintype "passive"))
      (node (ref "T24") (pin "3") (pinfunction "Emitter_3") (pintype "passive"))
    )
  )
)
